# MJ828_-_POC.net
KiCad netlist of a schematic drawn in EAGLE
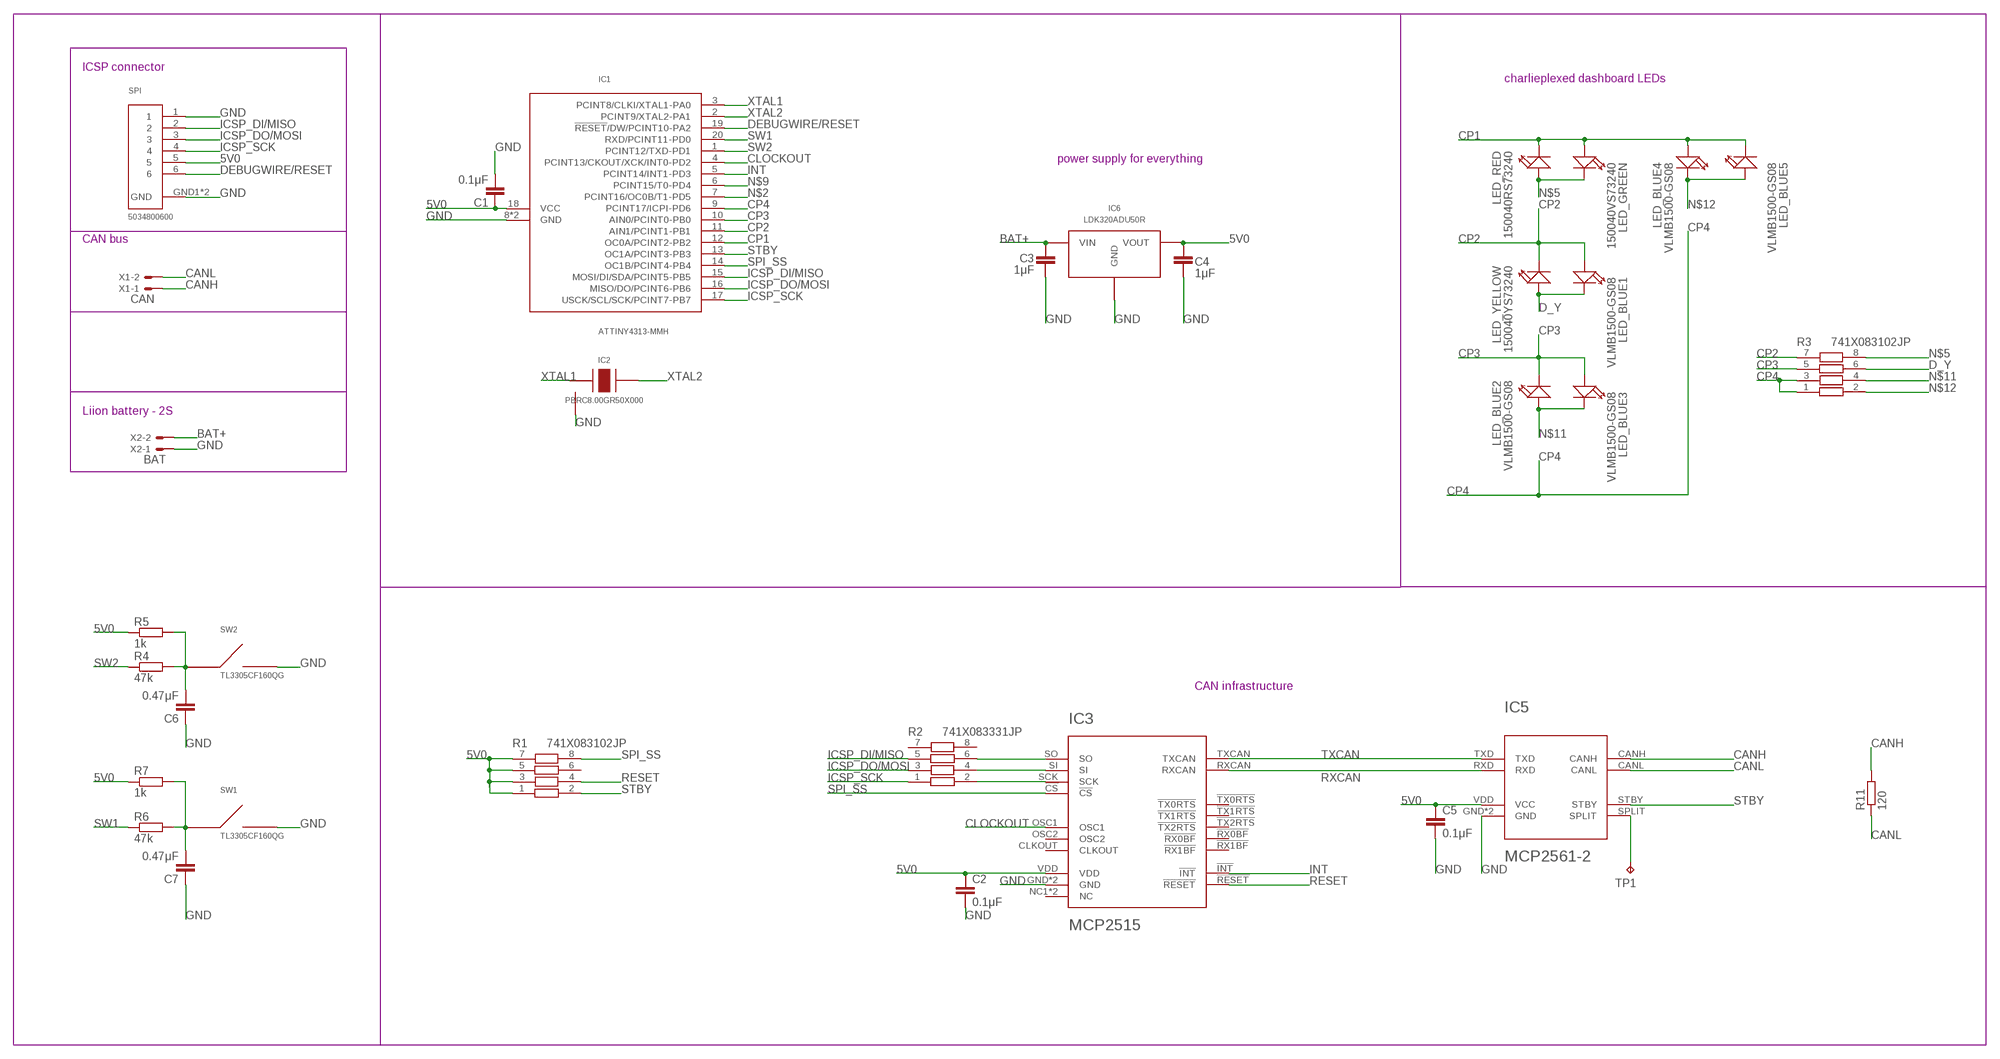
[diagram p0: schematic, sheet 1]

(export (version "E")
  (design (tool "Eeschema 10.0.6"))
  (components
    (comp (ref "C1")
      (value "0.1μF")
      (footprint "eagle-import:C0402")
      (libsource (lib "eagle-import") (part "C-EUC0402"))
    )
    (comp (ref "C2")
      (value "0.1μF")
      (footprint "eagle-import:C0402")
      (libsource (lib "eagle-import") (part "C-EUC0402"))
    )
    (comp (ref "C3")
      (value "1μF")
      (footprint "eagle-import:C0402")
      (libsource (lib "eagle-import") (part "C-EUC0402"))
    )
    (comp (ref "C4")
      (value "1μF")
      (footprint "eagle-import:C0402")
      (libsource (lib "eagle-import") (part "C-EUC0402"))
    )
    (comp (ref "C5")
      (value "0.1μF")
      (footprint "eagle-import:C0402")
      (libsource (lib "eagle-import") (part "C-EUC0402"))
    )
    (comp (ref "C6")
      (value "0.47μF")
      (footprint "eagle-import:C0402")
      (libsource (lib "eagle-import") (part "C-EUC0402"))
    )
    (comp (ref "C7")
      (value "0.47μF")
      (footprint "eagle-import:C0402")
      (libsource (lib "eagle-import") (part "C-EUC0402"))
    )
    (comp (ref "IC1")
      (value "ATTINY4313-MMH")
      (footprint "eagle-import:VQFN-20")
      (fields (field (name "SPICEPREFIX") "X"))
      (libsource (lib "eagle-import") (part "ATTINY4313VQFN-20"))
    )
    (comp (ref "IC2")
      (value "PBRC8.00GR50X000")
      (footprint "eagle-import:SMT")
      (libsource (lib "eagle-import") (part "PRQV"))
    )
    (comp (ref "IC3")
      (value "MCP2515")
      (footprint "eagle-import:QFN20")
      (libsource (lib "eagle-import") (part "MCP2515-I-ML"))
    )
    (comp (ref "IC5")
      (value "MCP2561-2")
      (footprint "eagle-import:DFN10")
      (libsource (lib "eagle-import") (part "MCP2561-2"))
    )
    (comp (ref "IC6")
      (value "LDK320ADU50R")
      (footprint "eagle-import:SOT-89")
      (libsource (lib "eagle-import") (part "LDO"))
    )
    (comp (ref "LED_BLUE1")
      (value "VLMB1500-GS08")
      (footprint "eagle-import:LED-0402")
      (fields (field (name "MPN") "BL-HB337A-AV-TRB"))
      (libsource (lib "eagle-import") (part "SMD-LED-CLEAR-BLUE(0402)"))
    )
    (comp (ref "LED_BLUE2")
      (value "VLMB1500-GS08")
      (footprint "eagle-import:LED-0402")
      (fields (field (name "MPN") "BL-HB337A-AV-TRB"))
      (libsource (lib "eagle-import") (part "SMD-LED-CLEAR-BLUE(0402)"))
    )
    (comp (ref "LED_BLUE3")
      (value "VLMB1500-GS08")
      (footprint "eagle-import:LED-0402")
      (fields (field (name "MPN") "BL-HB337A-AV-TRB"))
      (libsource (lib "eagle-import") (part "SMD-LED-CLEAR-BLUE(0402)"))
    )
    (comp (ref "LED_BLUE4")
      (value "VLMB1500-GS08")
      (footprint "eagle-import:LED-0402")
      (fields (field (name "MPN") "BL-HB337A-AV-TRB"))
      (libsource (lib "eagle-import") (part "SMD-LED-CLEAR-BLUE(0402)"))
    )
    (comp (ref "LED_BLUE5")
      (value "VLMB1500-GS08")
      (footprint "eagle-import:LED-0402")
      (fields (field (name "MPN") "BL-HB337A-AV-TRB"))
      (libsource (lib "eagle-import") (part "SMD-LED-CLEAR-BLUE(0402)"))
    )
    (comp (ref "LED_GREEN")
      (value "150040VS73240")
      (footprint "eagle-import:LED-0402")
      (fields (field (name "MPN") "BL-HB337A-AV-TRB"))
      (libsource (lib "eagle-import") (part "SMD-LED-CLEAR-BLUE(0402)"))
    )
    (comp (ref "LED_RED")
      (value "150040RS73240")
      (footprint "eagle-import:LED-0402")
      (fields (field (name "MPN") "BL-HB337A-AV-TRB"))
      (libsource (lib "eagle-import") (part "SMD-LED-CLEAR-BLUE(0402)"))
    )
    (comp (ref "LED_YELLOW")
      (value "150040YS73240")
      (footprint "eagle-import:LED-0402")
      (fields (field (name "MPN") "BL-HB337A-AV-TRB"))
      (libsource (lib "eagle-import") (part "SMD-LED-CLEAR-BLUE(0402)"))
    )
    (comp (ref "R1")
      (value "741X083102JP")
      (footprint "eagle-import:0402")
      (libsource (lib "eagle-import") (part "741X083331JP"))
    )
    (comp (ref "R2")
      (value "741X083331JP")
      (footprint "eagle-import:0402")
      (libsource (lib "eagle-import") (part "741X083331JP"))
    )
    (comp (ref "R3")
      (value "741X083102JP")
      (footprint "eagle-import:0402")
      (libsource (lib "eagle-import") (part "741X083331JP"))
    )
    (comp (ref "R4")
      (value "47k")
      (footprint "eagle-import:R0402")
      (libsource (lib "eagle-import") (part "R-EU_R0402"))
    )
    (comp (ref "R5")
      (value "1k")
      (footprint "eagle-import:R0402")
      (libsource (lib "eagle-import") (part "R-EU_R0402"))
    )
    (comp (ref "R6")
      (value "47k")
      (footprint "eagle-import:R0402")
      (libsource (lib "eagle-import") (part "R-EU_R0402"))
    )
    (comp (ref "R7")
      (value "1k")
      (footprint "eagle-import:R0402")
      (libsource (lib "eagle-import") (part "R-EU_R0402"))
    )
    (comp (ref "R11")
      (value "120")
      (footprint "eagle-import:R0805")
      (libsource (lib "eagle-import") (part "R-EU_R0805"))
    )
    (comp (ref "SPI")
      (value "5034800600")
      (footprint "eagle-import:SMT")
      (libsource (lib "eagle-import") (part "5034800600"))
    )
    (comp (ref "SW1")
      (value "TL3305CF160QG")
      (footprint "eagle-import:SMD")
      (libsource (lib "eagle-import") (part "TL3305-844809"))
    )
    (comp (ref "SW2")
      (value "TL3305CF160QG")
      (footprint "eagle-import:SMD")
      (libsource (lib "eagle-import") (part "TL3305-844809"))
    )
    (comp (ref "TP1")
      (value "TPB2,54")
      (footprint "eagle-import:B2,54")
      (libsource (lib "eagle-import") (part "TPB2,54"))
    )
    (comp (ref "X1")
      (value "CAN")
      (footprint "eagle-import:22-23-2021")
      (fields (field (name "MF") "MOLEX") (field (name "MPN") "22-23-2021"))
      (libsource (lib "eagle-import") (part "22-23-2021"))
    )
    (comp (ref "X2")
      (value "BAT")
      (footprint "eagle-import:22-23-2021")
      (fields (field (name "MF") "MOLEX") (field (name "MPN") "22-23-2021"))
      (libsource (lib "eagle-import") (part "22-23-2021"))
    )
  )
  (nets
    (net (code "1") (name "/5V0") (class "Default")
      (node (ref "C1") (pin "1") (pinfunction "1_1") (pintype "passive"))
      (node (ref "C2") (pin "1") (pinfunction "1_1") (pintype "passive"))
      (node (ref "C4") (pin "2") (pinfunction "2_2") (pintype "passive"))
      (node (ref "C5") (pin "1") (pinfunction "1_1") (pintype "passive"))
      (node (ref "IC1") (pin "18") (pinfunction "VCC_18") (pintype "bidirectional"))
      (node (ref "IC3") (pin "VDD") (pinfunction "VDD_VDD") (pintype "power_in"))
      (node (ref "IC5") (pin "VDD") (pinfunction "VCC_VDD") (pintype "power_in"))
      (node (ref "IC6") (pin "VOUT") (pinfunction "VOUT_VOUT") (pintype "bidirectional"))
      (node (ref "R1") (pin "1") (pinfunction "1_1") (pintype "bidirectional"))
      (node (ref "R1") (pin "3") (pinfunction "3_3") (pintype "bidirectional"))
      (node (ref "R1") (pin "5") (pinfunction "5_5") (pintype "bidirectional"))
      (node (ref "R1") (pin "7") (pinfunction "7_7") (pintype "bidirectional"))
      (node (ref "R5") (pin "1") (pinfunction "1_1") (pintype "passive"))
      (node (ref "R7") (pin "1") (pinfunction "1_1") (pintype "passive"))
      (node (ref "SPI") (pin "5") (pinfunction "5_5") (pintype "bidirectional"))
    )
    (net (code "2") (name "/BAT+") (class "Default")
      (node (ref "C3") (pin "1") (pinfunction "1_1") (pintype "passive"))
      (node (ref "IC6") (pin "VIN") (pinfunction "VIN_VIN") (pintype "bidirectional"))
      (node (ref "X2") (pin "2") (pinfunction "S_2") (pintype "passive"))
    )
    (net (code "3") (name "/CANH") (class "Default")
      (node (ref "IC5") (pin "CANH") (pinfunction "CANH_CANH") (pintype "bidirectional"))
      (node (ref "R11") (pin "2") (pinfunction "2_2") (pintype "passive"))
      (node (ref "X1") (pin "1") (pinfunction "S_1") (pintype "passive"))
    )
    (net (code "4") (name "/CANL") (class "Default")
      (node (ref "IC5") (pin "CANL") (pinfunction "CANL_CANL") (pintype "bidirectional"))
      (node (ref "R11") (pin "1") (pinfunction "1_1") (pintype "passive"))
      (node (ref "X1") (pin "2") (pinfunction "S_2") (pintype "passive"))
    )
    (net (code "5") (name "/CLOCKOUT") (class "Default")
      (node (ref "IC1") (pin "4") (pinfunction "PCINT13/CKOUT/XCK/INT0-PD2_4") (pintype "bidirectional"))
      (node (ref "IC3") (pin "OSC1") (pinfunction "OSC1_OSC1") (pintype "bidirectional"))
    )
    (net (code "6") (name "/CP1") (class "Default")
      (node (ref "IC1") (pin "12") (pinfunction "OC0A/PCINT2-PB2_12") (pintype "bidirectional"))
      (node (ref "LED_BLUE4") (pin "+") (pinfunction "+_+") (pintype "passive"))
      (node (ref "LED_BLUE5") (pin "-") (pinfunction "-_-") (pintype "passive"))
      (node (ref "LED_GREEN") (pin "+") (pinfunction "+_+") (pintype "passive"))
      (node (ref "LED_RED") (pin "-") (pinfunction "-_-") (pintype "passive"))
    )
    (net (code "7") (name "/CP2") (class "Default")
      (node (ref "IC1") (pin "11") (pinfunction "AIN1/PCINT1-PB1_11") (pintype "bidirectional"))
      (node (ref "LED_BLUE1") (pin "+") (pinfunction "+_+") (pintype "passive"))
      (node (ref "LED_YELLOW") (pin "-") (pinfunction "-_-") (pintype "passive"))
      (node (ref "R3") (pin "7") (pinfunction "7_7") (pintype "bidirectional"))
    )
    (net (code "8") (name "/CP3") (class "Default")
      (node (ref "IC1") (pin "10") (pinfunction "AIN0/PCINT0-PB0_10") (pintype "bidirectional"))
      (node (ref "LED_BLUE2") (pin "-") (pinfunction "-_-") (pintype "passive"))
      (node (ref "LED_BLUE3") (pin "+") (pinfunction "+_+") (pintype "passive"))
      (node (ref "R3") (pin "5") (pinfunction "5_5") (pintype "bidirectional"))
    )
    (net (code "9") (name "/CP4") (class "Default")
      (node (ref "IC1") (pin "9") (pinfunction "PCINT17/ICPI-PD6_9") (pintype "bidirectional"))
      (node (ref "R3") (pin "1") (pinfunction "1_1") (pintype "bidirectional"))
      (node (ref "R3") (pin "3") (pinfunction "3_3") (pintype "bidirectional"))
    )
    (net (code "10") (name "/DEBUGWIRE{slash}RESET") (class "Default")
      (node (ref "IC1") (pin "19") (pinfunction "~{RESET}/DW/PCINT10-PA2_19") (pintype "bidirectional"))
      (node (ref "SPI") (pin "6") (pinfunction "6_6") (pintype "bidirectional"))
    )
    (net (code "11") (name "/D_Y") (class "Default")
      (node (ref "LED_BLUE1") (pin "-") (pinfunction "-_-") (pintype "passive"))
      (node (ref "LED_YELLOW") (pin "+") (pinfunction "+_+") (pintype "passive"))
      (node (ref "R3") (pin "6") (pinfunction "6_6") (pintype "bidirectional"))
    )
    (net (code "12") (name "/GND") (class "Default")
      (node (ref "C1") (pin "2") (pinfunction "2_2") (pintype "passive"))
      (node (ref "C2") (pin "2") (pinfunction "2_2") (pintype "passive"))
      (node (ref "C3") (pin "2") (pinfunction "2_2") (pintype "passive"))
      (node (ref "C4") (pin "1") (pinfunction "1_1") (pintype "passive"))
      (node (ref "C5") (pin "2") (pinfunction "2_2") (pintype "passive"))
      (node (ref "C6") (pin "1") (pinfunction "1_1") (pintype "passive"))
      (node (ref "C7") (pin "1") (pinfunction "1_1") (pintype "passive"))
      (node (ref "IC1") (pin "8") (pinfunction "GND_8") (pintype "bidirectional"))
      (node (ref "IC1") (pin "GND") (pinfunction "GND_GND") (pintype "bidirectional"))
      (node (ref "IC2") (pin "GND") (pinfunction "GND_GND") (pintype "bidirectional"))
      (node (ref "IC3") (pin "GND") (pinfunction "GND_GND") (pintype "power_in"))
      (node (ref "IC3") (pin "GND6") (pinfunction "GND_GND6") (pintype "power_in"))
      (node (ref "IC5") (pin "GND") (pinfunction "GND_GND") (pintype "power_in"))
      (node (ref "IC5") (pin "VSS") (pinfunction "GND_VSS") (pintype "power_in"))
      (node (ref "IC6") (pin "GND") (pinfunction "GND_GND") (pintype "bidirectional"))
      (node (ref "SPI") (pin "1") (pinfunction "1_1") (pintype "bidirectional"))
      (node (ref "SPI") (pin "GND1") (pinfunction "GND_GND1") (pintype "bidirectional"))
      (node (ref "SPI") (pin "GND2") (pinfunction "GND_GND2") (pintype "bidirectional"))
      (node (ref "SW1") (pin "3") (pinfunction "P$2_3") (pintype "bidirectional"))
      (node (ref "SW1") (pin "4") (pinfunction "P$2_4") (pintype "bidirectional"))
      (node (ref "SW2") (pin "3") (pinfunction "P$2_3") (pintype "bidirectional"))
      (node (ref "SW2") (pin "4") (pinfunction "P$2_4") (pintype "bidirectional"))
      (node (ref "X2") (pin "1") (pinfunction "S_1") (pintype "passive"))
    )
    (net (code "13") (name "/ICSP_DI{slash}MISO") (class "Default")
      (node (ref "IC1") (pin "15") (pinfunction "MOSI/DI/SDA/PCINT5-PB5_15") (pintype "bidirectional"))
      (node (ref "R2") (pin "5") (pinfunction "5_5") (pintype "bidirectional"))
      (node (ref "SPI") (pin "2") (pinfunction "2_2") (pintype "bidirectional"))
    )
    (net (code "14") (name "/ICSP_DO{slash}MOSI") (class "Default")
      (node (ref "IC1") (pin "16") (pinfunction "MISO/DO/PCINT6-PB6_16") (pintype "bidirectional"))
      (node (ref "R2") (pin "3") (pinfunction "3_3") (pintype "bidirectional"))
      (node (ref "SPI") (pin "3") (pinfunction "3_3") (pintype "bidirectional"))
    )
    (net (code "15") (name "/ICSP_SCK") (class "Default")
      (node (ref "IC1") (pin "17") (pinfunction "USCK/SCL/SCK/PCINT7-PB7_17") (pintype "bidirectional"))
      (node (ref "R2") (pin "1") (pinfunction "1_1") (pintype "bidirectional"))
      (node (ref "SPI") (pin "4") (pinfunction "4_4") (pintype "bidirectional"))
    )
    (net (code "16") (name "/INT") (class "Default")
      (node (ref "IC1") (pin "5") (pinfunction "PCINT14/INT1-PD3_5") (pintype "bidirectional"))
      (node (ref "IC3") (pin "!INT!") (pinfunction "~{INT}_!INT!") (pintype "bidirectional"))
    )
    (net (code "17") (name "/N$2") (class "Default")
      (node (ref "IC1") (pin "7") (pinfunction "PCINT16/OC0B/T1-PD5_7") (pintype "bidirectional"))
    )
    (net (code "18") (name "/N$5") (class "Default")
      (node (ref "LED_GREEN") (pin "-") (pinfunction "-_-") (pintype "passive"))
      (node (ref "LED_RED") (pin "+") (pinfunction "+_+") (pintype "passive"))
      (node (ref "R3") (pin "8") (pinfunction "8_8") (pintype "bidirectional"))
    )
    (net (code "19") (name "/N$9") (class "Default")
      (node (ref "IC1") (pin "6") (pinfunction "PCINT15/T0-PD4_6") (pintype "bidirectional"))
    )
    (net (code "20") (name "/N$11") (class "Default")
      (node (ref "LED_BLUE2") (pin "+") (pinfunction "+_+") (pintype "passive"))
      (node (ref "LED_BLUE3") (pin "-") (pinfunction "-_-") (pintype "passive"))
      (node (ref "R3") (pin "4") (pinfunction "4_4") (pintype "bidirectional"))
    )
    (net (code "21") (name "/N$12") (class "Default")
      (node (ref "LED_BLUE4") (pin "-") (pinfunction "-_-") (pintype "passive"))
      (node (ref "LED_BLUE5") (pin "+") (pinfunction "+_+") (pintype "passive"))
      (node (ref "R3") (pin "2") (pinfunction "2_2") (pintype "bidirectional"))
    )
    (net (code "22") (name "/RESET") (class "Default")
      (node (ref "IC3") (pin "!RESET!") (pinfunction "~{RESET}_!RESET!") (pintype "bidirectional"))
      (node (ref "R1") (pin "4") (pinfunction "4_4") (pintype "bidirectional"))
    )
    (net (code "23") (name "/RXCAN") (class "Default")
      (node (ref "IC3") (pin "RXCAN") (pinfunction "RXCAN_RXCAN") (pintype "input"))
      (node (ref "IC5") (pin "RXD") (pinfunction "RXD_RXD") (pintype "output"))
    )
    (net (code "24") (name "/SPI_SS") (class "Default")
      (node (ref "IC1") (pin "14") (pinfunction "OC1B/PCINT4-PB4_14") (pintype "bidirectional"))
      (node (ref "IC3") (pin "!CS!") (pinfunction "~{CS}_!CS!") (pintype "bidirectional"))
      (node (ref "R1") (pin "8") (pinfunction "8_8") (pintype "bidirectional"))
    )
    (net (code "25") (name "/STBY") (class "Default")
      (node (ref "IC1") (pin "13") (pinfunction "OC1A/PCINT3-PB3_13") (pintype "bidirectional"))
      (node (ref "IC5") (pin "STBY") (pinfunction "STBY_STBY") (pintype "bidirectional"))
      (node (ref "R1") (pin "2") (pinfunction "2_2") (pintype "bidirectional"))
    )
    (net (code "26") (name "/SW1") (class "Default")
      (node (ref "IC1") (pin "20") (pinfunction "RXD/PCINT11-PD0_20") (pintype "bidirectional"))
      (node (ref "R6") (pin "1") (pinfunction "1_1") (pintype "passive"))
    )
    (net (code "27") (name "/SW2") (class "Default")
      (node (ref "IC1") (pin "1") (pinfunction "PCINT12/TXD-PD1_1") (pintype "bidirectional"))
      (node (ref "R4") (pin "1") (pinfunction "1_1") (pintype "passive"))
    )
    (net (code "28") (name "/TXCAN") (class "Default")
      (node (ref "IC3") (pin "TXCAN") (pinfunction "TXCAN_TXCAN") (pintype "output"))
      (node (ref "IC5") (pin "TXD") (pinfunction "TXD_TXD") (pintype "input"))
    )
    (net (code "29") (name "/XTAL1") (class "Default")
      (node (ref "IC1") (pin "3") (pinfunction "PCINT8/CLKI/XTAL1-PA0_3") (pintype "bidirectional"))
      (node (ref "IC2") (pin "XTAL1") (pinfunction "XTAL1_XTAL1") (pintype "bidirectional"))
    )
    (net (code "30") (name "/XTAL2") (class "Default")
      (node (ref "IC1") (pin "2") (pinfunction "PCINT9/XTAL2-PA1_2") (pintype "bidirectional"))
      (node (ref "IC2") (pin "XTAL2") (pinfunction "XTAL2_XTAL2") (pintype "bidirectional"))
    )
    (net (code "31") (name "Net-(C6-Pad2)") (class "Default")
      (node (ref "C6") (pin "2") (pinfunction "2_2") (pintype "passive"))
      (node (ref "R4") (pin "2") (pinfunction "2_2") (pintype "passive"))
      (node (ref "R5") (pin "2") (pinfunction "2_2") (pintype "passive"))
      (node (ref "SW2") (pin "1") (pinfunction "P$1_1") (pintype "bidirectional"))
      (node (ref "SW2") (pin "2") (pinfunction "P$1_2") (pintype "bidirectional"))
    )
    (net (code "32") (name "Net-(C7-Pad2)") (class "Default")
      (node (ref "C7") (pin "2") (pinfunction "2_2") (pintype "passive"))
      (node (ref "R6") (pin "2") (pinfunction "2_2") (pintype "passive"))
      (node (ref "R7") (pin "2") (pinfunction "2_2") (pintype "passive"))
      (node (ref "SW1") (pin "1") (pinfunction "P$1_1") (pintype "bidirectional"))
      (node (ref "SW1") (pin "2") (pinfunction "P$1_2") (pintype "bidirectional"))
    )
    (net (code "33") (name "Net-(IC3-PadSCK)") (class "Default")
      (node (ref "IC3") (pin "SCK") (pinfunction "SCK_SCK") (pintype "bidirectional"))
      (node (ref "R2") (pin "2") (pinfunction "2_2") (pintype "bidirectional"))
    )
    (net (code "34") (name "Net-(IC3-PadSI)") (class "Default")
      (node (ref "IC3") (pin "SI") (pinfunction "SI_SI") (pintype "input"))
      (node (ref "R2") (pin "4") (pinfunction "4_4") (pintype "bidirectional"))
    )
    (net (code "35") (name "Net-(IC3-PadSO)") (class "Default")
      (node (ref "IC3") (pin "SO") (pinfunction "SO_SO") (pintype "output"))
      (node (ref "R2") (pin "6") (pinfunction "6_6") (pintype "bidirectional"))
    )
    (net (code "36") (name "Net-(IC5-PadSPLIT)") (class "Default")
      (node (ref "IC5") (pin "SPLIT") (pinfunction "SPLIT_SPLIT") (pintype "bidirectional"))
      (node (ref "TP1") (pin "TP") (pinfunction "TP_TP") (pintype "input"))
    )
    (net (code "37") (name "unconnected-(IC3-NC-PadNC1)") (class "Default")
      (node (ref "IC3") (pin "NC1") (pinfunction "NC_NC1") (pintype "no_connect"))
    )
    (net (code "38") (name "unconnected-(IC3-NC-PadNC2)") (class "Default")
      (node (ref "IC3") (pin "NC2") (pinfunction "NC_NC2") (pintype "no_connect"))
    )
    (net (code "39") (name "unconnected-(IC3-PadCLKOUT)") (class "Default")
      (node (ref "IC3") (pin "CLKOUT") (pinfunction "CLKOUT_CLKOUT") (pintype "bidirectional"))
    )
    (net (code "40") (name "unconnected-(IC3-PadOSC2)") (class "Default")
      (node (ref "IC3") (pin "OSC2") (pinfunction "OSC2_OSC2") (pintype "bidirectional"))
    )
    (net (code "41") (name "unconnected-(IC3-~{RX0BF}-Pad!RX0BF!)") (class "Default")
      (node (ref "IC3") (pin "!RX0BF!") (pinfunction "~{RX0BF}_!RX0BF!") (pintype "bidirectional"))
    )
    (net (code "42") (name "unconnected-(IC3-~{RX1BF}-Pad!RX1BF!)") (class "Default")
      (node (ref "IC3") (pin "!RX1BF!") (pinfunction "~{RX1BF}_!RX1BF!") (pintype "bidirectional"))
    )
    (net (code "43") (name "unconnected-(IC3-~{TX0RTS}-Pad!TX0RTS!)") (class "Default")
      (node (ref "IC3") (pin "!TX0RTS!") (pinfunction "~{TX0RTS}_!TX0RTS!") (pintype "bidirectional"))
    )
    (net (code "44") (name "unconnected-(IC3-~{TX1RTS}-Pad!TX1RTS!)") (class "Default")
      (node (ref "IC3") (pin "!TX1RTS!") (pinfunction "~{TX1RTS}_!TX1RTS!") (pintype "bidirectional"))
    )
    (net (code "45") (name "unconnected-(IC3-~{TX2RTS}-Pad!TX2RTS!)") (class "Default")
      (node (ref "IC3") (pin "!TX2RTS!") (pinfunction "~{TX2RTS}_!TX2RTS!") (pintype "bidirectional"))
    )
    (net (code "46") (name "unconnected-(R1-Pad6)") (class "Default")
      (node (ref "R1") (pin "6") (pinfunction "6_6") (pintype "bidirectional"))
    )
    (net (code "47") (name "unconnected-(R2-Pad7)") (class "Default")
      (node (ref "R2") (pin "7") (pinfunction "7_7") (pintype "bidirectional"))
    )
    (net (code "48") (name "unconnected-(R2-Pad8)") (class "Default")
      (node (ref "R2") (pin "8") (pinfunction "8_8") (pintype "bidirectional"))
    )
  )
)
